# miniblink.net
KiCad netlist of a schematic drawn in EAGLE
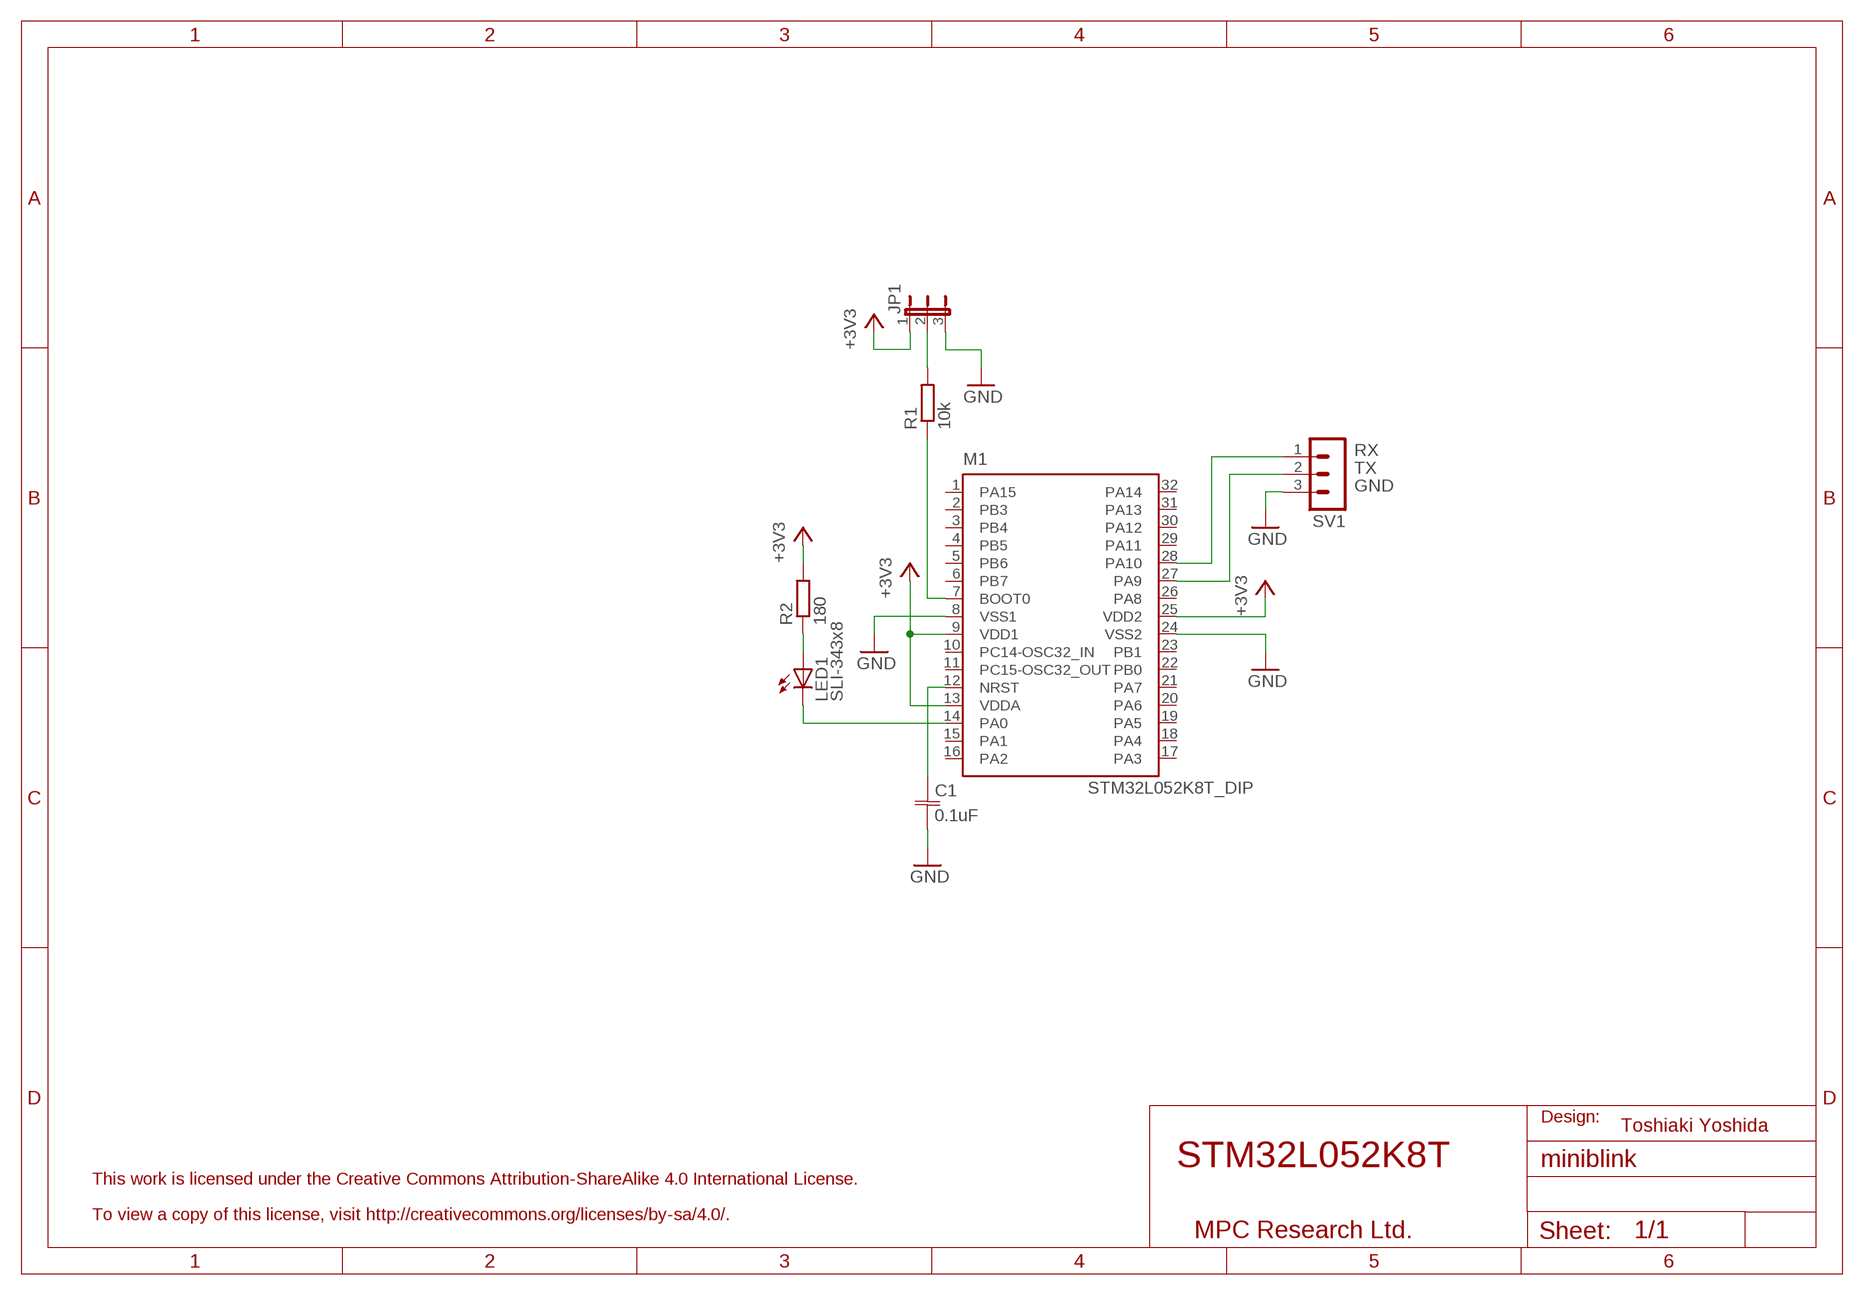
[diagram p0: schematic, sheet 1]

(export (version "E")
  (design (tool "Eeschema 10.0.6"))
  (components
    (comp (ref "C1")
      (value "0.1uF")
      (footprint "eagle-import:C050-024X044")
      (libsource (lib "eagle-import") (part "C-JIS050-024X044"))
    )
    (comp (ref "JP1")
      (value "JP2E")
      (footprint "eagle-import:JP2")
      (libsource (lib "eagle-import") (part "JP2E"))
    )
    (comp (ref "LED1")
      (value "SLI-343x8")
      (footprint "eagle-import:LED3MM")
      (libsource (lib "eagle-import") (part "LED3MM"))
    )
    (comp (ref "M1")
      (value "STM32L052K8T_DIP")
      (footprint "eagle-import:DIP32")
      (libsource (lib "eagle-import") (part "STM32L052K8T_DIP"))
    )
    (comp (ref "R1")
      (value "10k")
      (footprint "eagle-import:0207_2V")
      (libsource (lib "eagle-import") (part "R-EU_0207/2V"))
    )
    (comp (ref "R2")
      (value "180")
      (footprint "eagle-import:0207_2V")
      (libsource (lib "eagle-import") (part "R-EU_0207/2V"))
    )
    (comp (ref "SV1")
      (value "MA03-1")
      (footprint "eagle-import:MA03-1")
      (libsource (lib "eagle-import") (part "MA03-1"))
    )
  )
  (nets
    (net (code "1") (name "+3V3") (class "Default")
      (node (ref "JP1") (pin "1") (pinfunction "1_1") (pintype "passive"))
      (node (ref "M1") (pin "13") (pinfunction "VDDA_13") (pintype "power_in"))
      (node (ref "M1") (pin "25") (pinfunction "VDD2_25") (pintype "bidirectional"))
      (node (ref "M1") (pin "9") (pinfunction "VDD1_9") (pintype "power_in"))
      (node (ref "R2") (pin "2") (pinfunction "2_2") (pintype "passive"))
    )
    (net (code "2") (name "GND") (class "Default")
      (node (ref "C1") (pin "2") (pinfunction "2_2") (pintype "passive"))
      (node (ref "JP1") (pin "3") (pinfunction "3_3") (pintype "passive"))
      (node (ref "M1") (pin "24") (pinfunction "VSS2_24") (pintype "power_in"))
      (node (ref "M1") (pin "8") (pinfunction "VSS1_8") (pintype "power_in"))
      (node (ref "SV1") (pin "3") (pinfunction "3_3") (pintype "passive"))
    )
    (net (code "3") (name "Net-(JP1-Pad2)") (class "Default")
      (node (ref "JP1") (pin "2") (pinfunction "2_2") (pintype "passive"))
      (node (ref "R1") (pin "2") (pinfunction "2_2") (pintype "passive"))
    )
    (net (code "4") (name "Net-(LED1-C)") (class "Default")
      (node (ref "LED1") (pin "K") (pinfunction "C_K") (pintype "passive"))
      (node (ref "M1") (pin "14") (pinfunction "PA0_14") (pintype "bidirectional"))
    )
    (net (code "5") (name "Net-(LED1-PadA)") (class "Default")
      (node (ref "LED1") (pin "A") (pinfunction "A_A") (pintype "passive"))
      (node (ref "R2") (pin "1") (pinfunction "1_1") (pintype "passive"))
    )
    (net (code "6") (name "Net-(M1-BOOT0)") (class "Default")
      (node (ref "M1") (pin "7") (pinfunction "BOOT0_7") (pintype "bidirectional"))
      (node (ref "R1") (pin "1") (pinfunction "1_1") (pintype "passive"))
    )
    (net (code "7") (name "Net-(M1-NRST)") (class "Default")
      (node (ref "C1") (pin "1") (pinfunction "1_1") (pintype "passive"))
      (node (ref "M1") (pin "12") (pinfunction "NRST_12") (pintype "bidirectional"))
    )
    (net (code "8") (name "Net-(M1-PA9)") (class "Default")
      (node (ref "M1") (pin "27") (pinfunction "PA9_27") (pintype "bidirectional"))
      (node (ref "SV1") (pin "2") (pinfunction "2_2") (pintype "passive"))
    )
    (net (code "9") (name "Net-(M1-PA10)") (class "Default")
      (node (ref "M1") (pin "28") (pinfunction "PA10_28") (pintype "bidirectional"))
      (node (ref "SV1") (pin "1") (pinfunction "1_1") (pintype "passive"))
    )
    (net (code "10") (name "unconnected-(M1-PA1-Pad15)") (class "Default")
      (node (ref "M1") (pin "15") (pinfunction "PA1_15") (pintype "bidirectional"))
    )
    (net (code "11") (name "unconnected-(M1-PA2-Pad16)") (class "Default")
      (node (ref "M1") (pin "16") (pinfunction "PA2_16") (pintype "bidirectional"))
    )
    (net (code "12") (name "unconnected-(M1-PA3-Pad17)") (class "Default")
      (node (ref "M1") (pin "17") (pinfunction "PA3_17") (pintype "bidirectional"))
    )
    (net (code "13") (name "unconnected-(M1-PA4-Pad18)") (class "Default")
      (node (ref "M1") (pin "18") (pinfunction "PA4_18") (pintype "bidirectional"))
    )
    (net (code "14") (name "unconnected-(M1-PA5-Pad19)") (class "Default")
      (node (ref "M1") (pin "19") (pinfunction "PA5_19") (pintype "bidirectional"))
    )
    (net (code "15") (name "unconnected-(M1-PA6-Pad20)") (class "Default")
      (node (ref "M1") (pin "20") (pinfunction "PA6_20") (pintype "bidirectional"))
    )
    (net (code "16") (name "unconnected-(M1-PA7-Pad21)") (class "Default")
      (node (ref "M1") (pin "21") (pinfunction "PA7_21") (pintype "bidirectional"))
    )
    (net (code "17") (name "unconnected-(M1-PA8-Pad26)") (class "Default")
      (node (ref "M1") (pin "26") (pinfunction "PA8_26") (pintype "bidirectional"))
    )
    (net (code "18") (name "unconnected-(M1-PA11-Pad29)") (class "Default")
      (node (ref "M1") (pin "29") (pinfunction "PA11_29") (pintype "bidirectional"))
    )
    (net (code "19") (name "unconnected-(M1-PA12-Pad30)") (class "Default")
      (node (ref "M1") (pin "30") (pinfunction "PA12_30") (pintype "bidirectional"))
    )
    (net (code "20") (name "unconnected-(M1-PA13-Pad31)") (class "Default")
      (node (ref "M1") (pin "31") (pinfunction "PA13_31") (pintype "bidirectional"))
    )
    (net (code "21") (name "unconnected-(M1-PA14-Pad32)") (class "Default")
      (node (ref "M1") (pin "32") (pinfunction "PA14_32") (pintype "bidirectional"))
    )
    (net (code "22") (name "unconnected-(M1-PA15-Pad1)") (class "Default")
      (node (ref "M1") (pin "1") (pinfunction "PA15_1") (pintype "bidirectional"))
    )
    (net (code "23") (name "unconnected-(M1-PB0-Pad22)") (class "Default")
      (node (ref "M1") (pin "22") (pinfunction "PB0_22") (pintype "bidirectional"))
    )
    (net (code "24") (name "unconnected-(M1-PB1-Pad23)") (class "Default")
      (node (ref "M1") (pin "23") (pinfunction "PB1_23") (pintype "bidirectional"))
    )
    (net (code "25") (name "unconnected-(M1-PB3-Pad2)") (class "Default")
      (node (ref "M1") (pin "2") (pinfunction "PB3_2") (pintype "bidirectional"))
    )
    (net (code "26") (name "unconnected-(M1-PB4-Pad3)") (class "Default")
      (node (ref "M1") (pin "3") (pinfunction "PB4_3") (pintype "bidirectional"))
    )
    (net (code "27") (name "unconnected-(M1-PB5-Pad4)") (class "Default")
      (node (ref "M1") (pin "4") (pinfunction "PB5_4") (pintype "bidirectional"))
    )
    (net (code "28") (name "unconnected-(M1-PB6-Pad5)") (class "Default")
      (node (ref "M1") (pin "5") (pinfunction "PB6_5") (pintype "bidirectional"))
    )
    (net (code "29") (name "unconnected-(M1-PB7-Pad6)") (class "Default")
      (node (ref "M1") (pin "6") (pinfunction "PB7_6") (pintype "bidirectional"))
    )
    (net (code "30") (name "unconnected-(M1-PC14-OSC32_IN-Pad10)") (class "Default")
      (node (ref "M1") (pin "10") (pinfunction "PC14-OSC32_IN_10") (pintype "bidirectional"))
    )
    (net (code "31") (name "unconnected-(M1-PC15-OSC32_OUT-Pad11)") (class "Default")
      (node (ref "M1") (pin "11") (pinfunction "PC15-OSC32_OUT_11") (pintype "bidirectional"))
    )
  )
)
